# main.net
KiCad netlist of a schematic drawn in Altium Designer
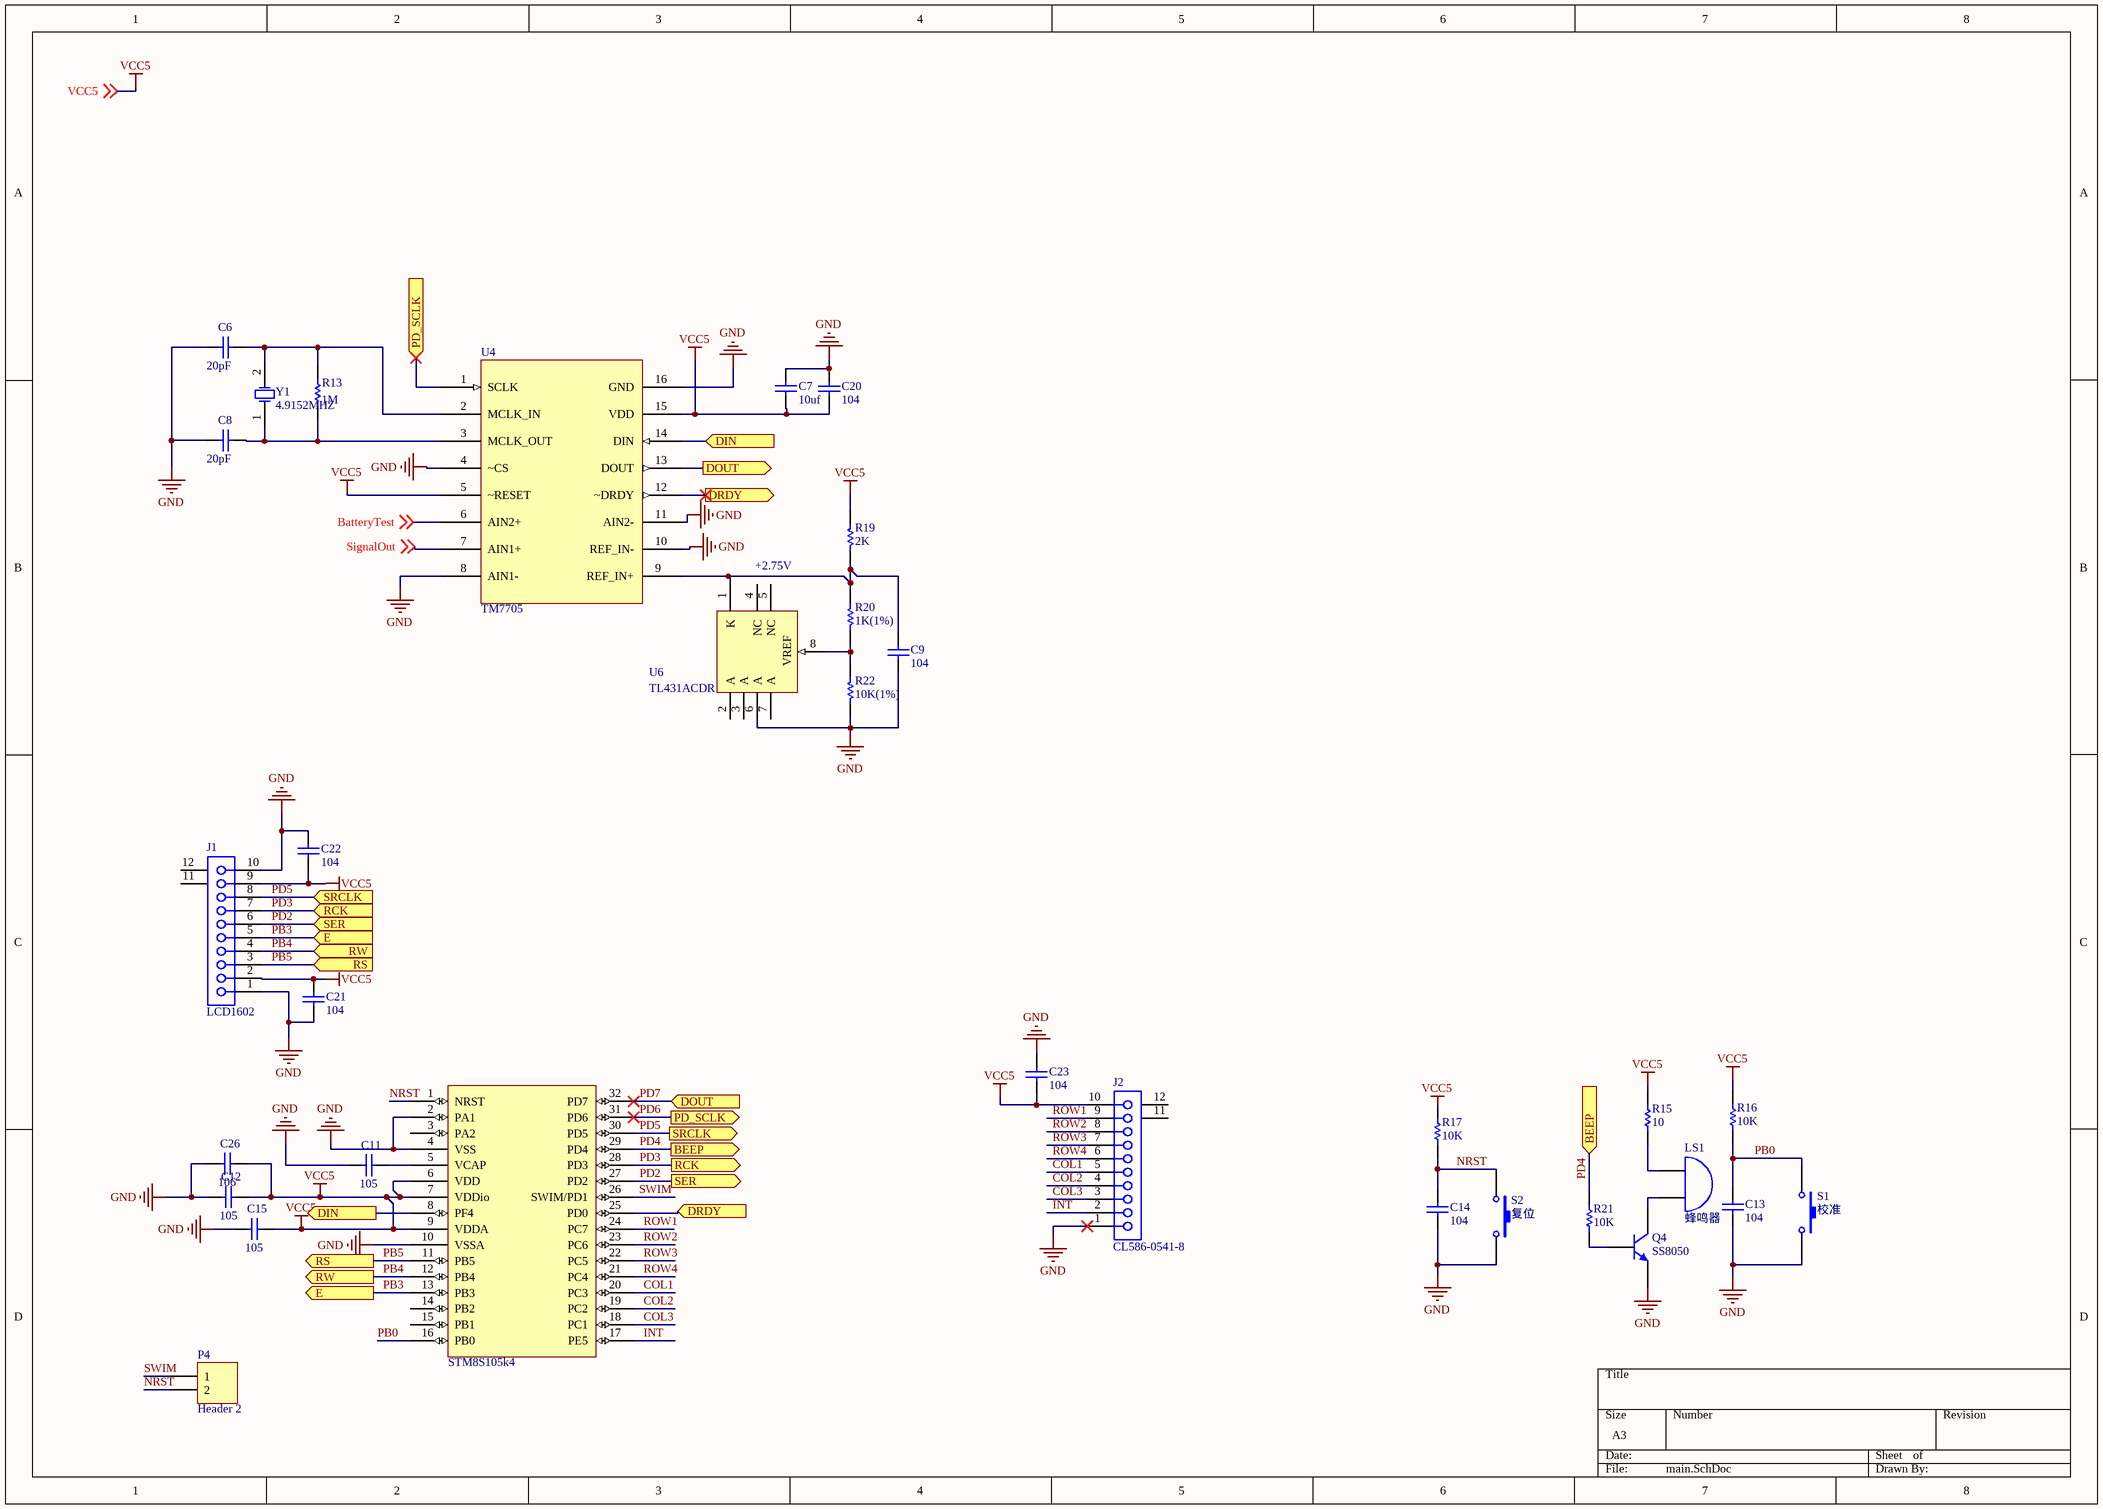
[diagram p0: main.SchDoc]

(export (version "E")
  (design (tool "Eeschema 10.0.6"))
  (components
    (comp (ref "C6")
      (value "20pF")
      (footprint "C0805")
      (description "Capacitor")
      (fields (field (name "Comment") "Cap") (field (name "PUBLISHER") "Altium Limited"))
      (libsource (lib "Miscellaneous Devices") (part "Cap"))
    )
    (comp (ref "C7")
      (value "10uf")
      (footprint "C0805")
      (description "Capacitor")
      (fields (field (name "Comment") "Cap") (field (name "PUBLISHER") "Altium Limited"))
      (libsource (lib "Miscellaneous Devices") (part "Cap"))
    )
    (comp (ref "C8")
      (value "20pF")
      (footprint "C0805")
      (description "Capacitor")
      (fields (field (name "Comment") "Cap") (field (name "PUBLISHER") "Altium Limited"))
      (libsource (lib "Miscellaneous Devices") (part "Cap"))
    )
    (comp (ref "C9")
      (value "104")
      (footprint "C0805")
      (description "Capacitor")
      (fields (field (name "Comment") "Cap") (field (name "PUBLISHER") "Altium Limited"))
      (libsource (lib "Miscellaneous Devices") (part "Cap"))
    )
    (comp (ref "C11")
      (value "105")
      (footprint "C0805")
      (description "Capacitor")
      (fields (field (name "Comment") "Cap") (field (name "PUBLISHER") "Altium Limited"))
      (libsource (lib "Miscellaneous Devices") (part "Cap"))
    )
    (comp (ref "C12")
      (value "105")
      (footprint "C0805")
      (description "Capacitor")
      (fields (field (name "Comment") "Cap") (field (name "PUBLISHER") "Altium Limited"))
      (libsource (lib "Miscellaneous Devices") (part "Cap"))
    )
    (comp (ref "C13")
      (value "104")
      (footprint "C0805")
      (description "Capacitor")
      (fields (field (name "Comment") "Cap") (field (name "PUBLISHER") "Altium Limited"))
      (libsource (lib "Miscellaneous Devices") (part "Cap"))
    )
    (comp (ref "C14")
      (value "104")
      (footprint "C0805")
      (description "Capacitor")
      (fields (field (name "Comment") "Cap") (field (name "PUBLISHER") "Altium Limited"))
      (libsource (lib "Miscellaneous Devices") (part "Cap"))
    )
    (comp (ref "C15")
      (value "105")
      (footprint "C0805")
      (description "Capacitor")
      (fields (field (name "Comment") "Cap") (field (name "PUBLISHER") "Altium Limited"))
      (libsource (lib "Miscellaneous Devices") (part "Cap"))
    )
    (comp (ref "C20")
      (value "104")
      (footprint "C0805")
      (description "Capacitor")
      (fields (field (name "Comment") "Cap") (field (name "PUBLISHER") "Altium Limited"))
      (libsource (lib "Miscellaneous Devices") (part "Cap"))
    )
    (comp (ref "C21")
      (value "104")
      (footprint "C0805")
      (description "Capacitor")
      (fields (field (name "Comment") "Cap") (field (name "PUBLISHER") "Altium Limited"))
      (libsource (lib "Miscellaneous Devices") (part "Cap"))
    )
    (comp (ref "C22")
      (value "104")
      (footprint "C0805")
      (description "Capacitor")
      (fields (field (name "Comment") "Cap") (field (name "PUBLISHER") "Altium Limited"))
      (libsource (lib "Miscellaneous Devices") (part "Cap"))
    )
    (comp (ref "C23")
      (value "104")
      (footprint "C0805")
      (description "Capacitor")
      (fields (field (name "Comment") "Cap") (field (name "PUBLISHER") "Altium Limited"))
      (libsource (lib "Miscellaneous Devices") (part "Cap"))
    )
    (comp (ref "C26")
      (value "106")
      (footprint "C0805")
      (description "Capacitor")
      (fields (field (name "Comment") "Cap") (field (name "PUBLISHER") "Altium Limited"))
      (libsource (lib "Miscellaneous Devices") (part "Cap"))
    )
    (comp (ref "J1")
      (value "LCD1602")
      (footprint "FH12-22(10)SA-1SH")
      (description "FH12 Series, \"Flip-Lock\" SMT/ZIF FFC/FPC Connector - 1.0mm Spaced Bottom Eccentric Contact")
      (fields (field (name "PUBLISHER") "Altium Limited"))
      (libsource (lib "HRS FPC-FFC FH12 Series") (part "CL586-0541-8"))
    )
    (comp (ref "J2")
      (value "CL586-0541-8")
      (footprint "FH12-22(10)SA-1SH")
      (description "FH12 Series, \"Flip-Lock\" SMT/ZIF FFC/FPC Connector - 1.0mm Spaced Bottom Eccentric Contact")
      (fields (field (name "PUBLISHER") "Altium Limited"))
      (libsource (lib "HRS FPC-FFC FH12 Series") (part "CL586-0541-8"))
    )
    (comp (ref "LS1")
      (value "蜂鸣器")
      (footprint "BELL")
      (description "Electrical Bell")
      (fields (field (name "PUBLISHER") "Altium Limited"))
      (libsource (lib "Miscellaneous Devices") (part "Bell"))
    )
    (comp (ref "P4")
      (value "Header 2")
      (footprint "HDR1X2")
      (description "Header, 2-Pin")
      (fields (field (name "PUBLISHER") "Altium Limited"))
      (libsource (lib "Miscellaneous Connectors") (part "Header 2"))
    )
    (comp (ref "Q4")
      (value "SS8050")
      (footprint "SOT-23_N")
      (description "NPN Bipolar Transistor")
      (fields (field (name "PUBLISHER") "Altium Limited"))
      (libsource (lib "Miscellaneous Devices") (part "NPN"))
    )
    (comp (ref "R13")
      (value "1M")
      (footprint "C1206")
      (description "Resistor")
      (fields (field (name "Comment") "Res1") (field (name "PUBLISHER") "Altium Limited"))
      (libsource (lib "Miscellaneous Devices") (part "Res1"))
    )
    (comp (ref "R15")
      (value "10")
      (footprint "C1206")
      (description "Resistor")
      (fields (field (name "Comment") "Res1") (field (name "PUBLISHER") "Altium Limited"))
      (libsource (lib "Miscellaneous Devices") (part "Res1"))
    )
    (comp (ref "R16")
      (value "10K")
      (footprint "6-0805_N")
      (description "Resistor")
      (fields (field (name "Comment") "Res1") (field (name "PUBLISHER") "Altium Limited"))
      (libsource (lib "Miscellaneous Devices") (part "Res1"))
    )
    (comp (ref "R17")
      (value "10K")
      (footprint "6-0805_N")
      (description "Resistor")
      (fields (field (name "Comment") "Res1") (field (name "PUBLISHER") "Altium Limited"))
      (libsource (lib "Miscellaneous Devices") (part "Res1"))
    )
    (comp (ref "R19")
      (value "2K")
      (footprint "6-0805_N")
      (description "Resistor")
      (fields (field (name "Comment") "Res1") (field (name "PUBLISHER") "Altium Limited"))
      (libsource (lib "Miscellaneous Devices") (part "Res1"))
    )
    (comp (ref "R20")
      (value "1K(1%)")
      (footprint "6-0805_N")
      (description "Resistor")
      (fields (field (name "Comment") "Res1") (field (name "PUBLISHER") "Altium Limited"))
      (libsource (lib "Miscellaneous Devices") (part "Res1"))
    )
    (comp (ref "R21")
      (value "10K")
      (footprint "6-0805_N")
      (description "Resistor")
      (fields (field (name "Comment") "Res1") (field (name "PUBLISHER") "Altium Limited"))
      (libsource (lib "Miscellaneous Devices") (part "Res1"))
    )
    (comp (ref "R22")
      (value "10K(1%)")
      (footprint "6-0805_N")
      (description "Resistor")
      (fields (field (name "Comment") "Res1") (field (name "PUBLISHER") "Altium Limited"))
      (libsource (lib "Miscellaneous Devices") (part "Res1"))
    )
    (comp (ref "S1")
      (value "校准")
      (footprint "buttin12*12")
      (description "Switch")
      (fields (field (name "PUBLISHER") "Altium Limited"))
      (libsource (lib "Miscellaneous Devices") (part "SW-PB"))
    )
    (comp (ref "S2")
      (value "复位")
      (footprint "buttin6*6")
      (description "Switch")
      (fields (field (name "PUBLISHER") "Altium Limited"))
      (libsource (lib "Miscellaneous Devices") (part "SW-PB"))
    )
    (comp (ref "STM1") (value "STM8S105k4") (footprint "LQFP32") (libsource (lib "self") (part "STM8S105k4")))
    (comp (ref "U4") (value "TM7705") (footprint "SO16_N") (libsource (lib "Schlib1") (part "TM7705")))
    (comp (ref "U6")
      (value "TL431ACDR")
      (footprint "D008_N")
      (description "Adjustable Precision Shunt Regulator")
      (fields (field (name "PUBLISHER") "Altium Limited"))
      (libsource (lib "TI Power Mgt Voltage Regulator") (part "TL431ACDR"))
    )
    (comp (ref "Y1")
      (value "4.9152MHZ")
      (footprint "XTAL-HC49US2")
      (description "Crystal Oscillator")
      (fields (field (name "PUBLISHER") "Altium Limited"))
      (libsource (lib "Miscellaneous Devices") (part "XTAL"))
    )
  )
  (nets
    (net (code "2") (name "/COL1") (class "Default")
      (node (ref "J2") (pin "5") (pinfunction "5_5") (pintype "passive"))
      (node (ref "STM1") (pin "20") (pinfunction "PC3_20") (pintype "bidirectional"))
    )
    (net (code "3") (name "/COL2") (class "Default")
      (node (ref "J2") (pin "4") (pinfunction "4_4") (pintype "passive"))
      (node (ref "STM1") (pin "19") (pinfunction "PC2_19") (pintype "bidirectional"))
    )
    (net (code "4") (name "/COL3") (class "Default")
      (node (ref "J2") (pin "3") (pinfunction "3_3") (pintype "passive"))
      (node (ref "STM1") (pin "18") (pinfunction "PC1_18") (pintype "bidirectional"))
    )
    (net (code "5") (name "/DIN") (class "Default")
      (node (ref "STM1") (pin "8") (pinfunction "PF4_8") (pintype "bidirectional"))
      (node (ref "U4") (pin "14") (pinfunction "DIN_14") (pintype "input"))
    )
    (net (code "6") (name "/DRDY") (class "Default")
      (node (ref "STM1") (pin "25") (pinfunction "PD0_25") (pintype "bidirectional"))
      (node (ref "U4") (pin "12") (pinfunction "~DRDY_12") (pintype "output"))
    )
    (net (code "7") (name "/INT") (class "Default")
      (node (ref "J2") (pin "2") (pinfunction "2_2") (pintype "passive"))
      (node (ref "STM1") (pin "17") (pinfunction "PE5_17") (pintype "bidirectional"))
    )
    (net (code "8") (name "/NRST") (class "Default")
      (node (ref "C14") (pin "2") (pinfunction "2_2") (pintype "passive"))
      (node (ref "P4") (pin "2") (pinfunction "2_2") (pintype "passive"))
      (node (ref "R17") (pin "2") (pinfunction "2_2") (pintype "passive"))
      (node (ref "S2") (pin "1") (pinfunction "1_1") (pintype "passive"))
      (node (ref "STM1") (pin "1") (pinfunction "NRST_1") (pintype "bidirectional"))
    )
    (net (code "9") (name "/PB0") (class "Default")
      (node (ref "C13") (pin "2") (pinfunction "2_2") (pintype "passive"))
      (node (ref "R16") (pin "2") (pinfunction "2_2") (pintype "passive"))
      (node (ref "S1") (pin "1") (pinfunction "1_1") (pintype "passive"))
      (node (ref "STM1") (pin "16") (pinfunction "PB0_16") (pintype "bidirectional"))
    )
    (net (code "10") (name "/PB3") (class "Default")
      (node (ref "J1") (pin "5") (pinfunction "5_5") (pintype "passive"))
      (node (ref "STM1") (pin "13") (pinfunction "PB3_13") (pintype "bidirectional"))
    )
    (net (code "11") (name "/PB4") (class "Default")
      (node (ref "J1") (pin "4") (pinfunction "4_4") (pintype "passive"))
      (node (ref "STM1") (pin "12") (pinfunction "PB4_12") (pintype "bidirectional"))
    )
    (net (code "12") (name "/PB5") (class "Default")
      (node (ref "J1") (pin "3") (pinfunction "3_3") (pintype "passive"))
      (node (ref "STM1") (pin "11") (pinfunction "PB5_11") (pintype "bidirectional"))
    )
    (net (code "13") (name "/PD2") (class "Default")
      (node (ref "J1") (pin "6") (pinfunction "6_6") (pintype "passive"))
      (node (ref "STM1") (pin "27") (pinfunction "PD2_27") (pintype "bidirectional"))
    )
    (net (code "14") (name "/PD3") (class "Default")
      (node (ref "J1") (pin "7") (pinfunction "7_7") (pintype "passive"))
      (node (ref "STM1") (pin "28") (pinfunction "PD3_28") (pintype "bidirectional"))
    )
    (net (code "15") (name "/PD4") (class "Default")
      (node (ref "R21") (pin "2") (pinfunction "2_2") (pintype "passive"))
      (node (ref "STM1") (pin "29") (pinfunction "PD4_29") (pintype "bidirectional"))
    )
    (net (code "16") (name "/PD5") (class "Default")
      (node (ref "J1") (pin "8") (pinfunction "8_8") (pintype "passive"))
      (node (ref "STM1") (pin "30") (pinfunction "PD5_30") (pintype "bidirectional"))
    )
    (net (code "17") (name "/PD6") (class "Default")
      (node (ref "STM1") (pin "31") (pinfunction "PD6_31") (pintype "bidirectional"))
      (node (ref "U4") (pin "1") (pinfunction "SCLK_1") (pintype "input"))
    )
    (net (code "18") (name "/PD7") (class "Default")
      (node (ref "STM1") (pin "32") (pinfunction "PD7_32") (pintype "bidirectional"))
      (node (ref "U4") (pin "13") (pinfunction "DOUT_13") (pintype "output"))
    )
    (net (code "19") (name "/ROW1") (class "Default")
      (node (ref "J2") (pin "9") (pinfunction "9_9") (pintype "passive"))
      (node (ref "STM1") (pin "24") (pinfunction "PC7_24") (pintype "bidirectional"))
    )
    (net (code "20") (name "/ROW2") (class "Default")
      (node (ref "J2") (pin "8") (pinfunction "8_8") (pintype "passive"))
      (node (ref "STM1") (pin "23") (pinfunction "PC6_23") (pintype "bidirectional"))
    )
    (net (code "21") (name "/ROW3") (class "Default")
      (node (ref "J2") (pin "7") (pinfunction "7_7") (pintype "passive"))
      (node (ref "STM1") (pin "22") (pinfunction "PC5_22") (pintype "bidirectional"))
    )
    (net (code "22") (name "/ROW4") (class "Default")
      (node (ref "J2") (pin "6") (pinfunction "6_6") (pintype "passive"))
      (node (ref "STM1") (pin "21") (pinfunction "PC4_21") (pintype "bidirectional"))
    )
    (net (code "23") (name "/SWIM") (class "Default")
      (node (ref "P4") (pin "1") (pinfunction "1_1") (pintype "passive"))
      (node (ref "STM1") (pin "26") (pinfunction "SWIM/PD1_26") (pintype "bidirectional"))
    )
    (net (code "24") (name "BatteryTest") (class "Default")
      (node (ref "U4") (pin "6") (pinfunction "AIN2+_6") (pintype "passive"))
    )
    (net (code "25") (name "GND") (class "Default")
      (node (ref "C11") (pin "1") (pinfunction "1_1") (pintype "passive"))
      (node (ref "C12") (pin "1") (pinfunction "1_1") (pintype "passive"))
      (node (ref "C13") (pin "1") (pinfunction "1_1") (pintype "passive"))
      (node (ref "C14") (pin "1") (pinfunction "1_1") (pintype "passive"))
      (node (ref "C15") (pin "1") (pinfunction "1_1") (pintype "passive"))
      (node (ref "C20") (pin "2") (pinfunction "2_2") (pintype "passive"))
      (node (ref "C21") (pin "2") (pinfunction "2_2") (pintype "passive"))
      (node (ref "C22") (pin "1") (pinfunction "1_1") (pintype "passive"))
      (node (ref "C23") (pin "2") (pinfunction "2_2") (pintype "passive"))
      (node (ref "C26") (pin "1") (pinfunction "1_1") (pintype "passive"))
      (node (ref "C6") (pin "1") (pinfunction "1_1") (pintype "passive"))
      (node (ref "C7") (pin "2") (pinfunction "2_2") (pintype "passive"))
      (node (ref "C8") (pin "1") (pinfunction "1_1") (pintype "passive"))
      (node (ref "C9") (pin "1") (pinfunction "1_1") (pintype "passive"))
      (node (ref "J1") (pin "1") (pinfunction "1_1") (pintype "passive"))
      (node (ref "J1") (pin "10") (pinfunction "10_10") (pintype "passive"))
      (node (ref "J2") (pin "1") (pinfunction "1_1") (pintype "passive"))
      (node (ref "Q4") (pin "3") (pinfunction "E_3") (pintype "passive"))
      (node (ref "R22") (pin "2") (pinfunction "2_2") (pintype "passive"))
      (node (ref "S1") (pin "2") (pinfunction "2_2") (pintype "passive"))
      (node (ref "S2") (pin "2") (pinfunction "2_2") (pintype "passive"))
      (node (ref "STM1") (pin "10") (pinfunction "VSSA_10") (pintype "passive"))
      (node (ref "STM1") (pin "2") (pinfunction "PA1_2") (pintype "bidirectional"))
      (node (ref "STM1") (pin "4") (pinfunction "VSS_4") (pintype "passive"))
      (node (ref "U4") (pin "10") (pinfunction "REF_IN-_10") (pintype "passive"))
      (node (ref "U4") (pin "11") (pinfunction "AIN2-_11") (pintype "passive"))
      (node (ref "U4") (pin "16") (pinfunction "GND_16") (pintype "passive"))
      (node (ref "U4") (pin "4") (pinfunction "~CS_4") (pintype "passive"))
      (node (ref "U4") (pin "8") (pinfunction "AIN1-_8") (pintype "passive"))
      (node (ref "U6") (pin "6") (pinfunction "A_6") (pintype "power_in"))
    )
    (net (code "26") (name "Net-(LS1-A)") (class "Default")
      (node (ref "LS1") (pin "1") (pinfunction "A_1") (pintype "passive"))
      (node (ref "R15") (pin "2") (pinfunction "2_2") (pintype "passive"))
    )
    (net (code "27") (name "Net-(LS1-B)") (class "Default")
      (node (ref "LS1") (pin "2") (pinfunction "B_2") (pintype "passive"))
      (node (ref "Q4") (pin "1") (pinfunction "C_1") (pintype "passive"))
    )
    (net (code "28") (name "Net-(Q4-B)") (class "Default")
      (node (ref "Q4") (pin "2") (pinfunction "B_2") (pintype "passive"))
      (node (ref "R21") (pin "1") (pinfunction "1_1") (pintype "passive"))
    )
    (net (code "29") (name "Net-(STM1-VCAP)") (class "Default")
      (node (ref "C11") (pin "2") (pinfunction "2_2") (pintype "passive"))
      (node (ref "STM1") (pin "5") (pinfunction "VCAP_5") (pintype "passive"))
    )
    (net (code "30") (name "Net-(U4-MCLK_IN)") (class "Default")
      (node (ref "C6") (pin "2") (pinfunction "2_2") (pintype "passive"))
      (node (ref "R13") (pin "1") (pinfunction "1_1") (pintype "passive"))
      (node (ref "U4") (pin "2") (pinfunction "MCLK_IN_2") (pintype "passive"))
      (node (ref "Y1") (pin "2") (pinfunction "OSC2_2") (pintype "passive"))
    )
    (net (code "31") (name "Net-(U4-MCLK_OUT)") (class "Default")
      (node (ref "C8") (pin "2") (pinfunction "2_2") (pintype "passive"))
      (node (ref "R13") (pin "2") (pinfunction "2_2") (pintype "passive"))
      (node (ref "U4") (pin "3") (pinfunction "MCLK_OUT_3") (pintype "passive"))
      (node (ref "Y1") (pin "1") (pinfunction "OSC1_1") (pintype "passive"))
    )
    (net (code "32") (name "Net-(U4-REF_IN+)") (class "Default")
      (node (ref "C9") (pin "2") (pinfunction "2_2") (pintype "passive"))
      (node (ref "R19") (pin "2") (pinfunction "2_2") (pintype "passive"))
      (node (ref "R20") (pin "1") (pinfunction "1_1") (pintype "passive"))
      (node (ref "U4") (pin "9") (pinfunction "REF_IN+_9") (pintype "passive"))
      (node (ref "U6") (pin "1") (pinfunction "K_1") (pintype "power_in"))
    )
    (net (code "33") (name "Net-(U6-VREF)") (class "Default")
      (node (ref "R20") (pin "2") (pinfunction "2_2") (pintype "passive"))
      (node (ref "R22") (pin "1") (pinfunction "1_1") (pintype "passive"))
      (node (ref "U6") (pin "8") (pinfunction "VREF_8") (pintype "input"))
    )
    (net (code "34") (name "SignalOut") (class "Default")
      (node (ref "U4") (pin "7") (pinfunction "AIN1+_7") (pintype "passive"))
    )
    (net (code "35") (name "VCC5") (class "Default")
      (node (ref "C12") (pin "2") (pinfunction "2_2") (pintype "passive"))
      (node (ref "C15") (pin "2") (pinfunction "2_2") (pintype "passive"))
      (node (ref "C20") (pin "1") (pinfunction "1_1") (pintype "passive"))
      (node (ref "C21") (pin "1") (pinfunction "1_1") (pintype "passive"))
      (node (ref "C22") (pin "2") (pinfunction "2_2") (pintype "passive"))
      (node (ref "C23") (pin "1") (pinfunction "1_1") (pintype "passive"))
      (node (ref "C26") (pin "2") (pinfunction "2_2") (pintype "passive"))
      (node (ref "C7") (pin "1") (pinfunction "1_1") (pintype "passive"))
      (node (ref "J1") (pin "2") (pinfunction "2_2") (pintype "passive"))
      (node (ref "J1") (pin "9") (pinfunction "9_9") (pintype "passive"))
      (node (ref "J2") (pin "10") (pinfunction "10_10") (pintype "passive"))
      (node (ref "R15") (pin "1") (pinfunction "1_1") (pintype "passive"))
      (node (ref "R16") (pin "1") (pinfunction "1_1") (pintype "passive"))
      (node (ref "R17") (pin "1") (pinfunction "1_1") (pintype "passive"))
      (node (ref "R19") (pin "1") (pinfunction "1_1") (pintype "passive"))
      (node (ref "STM1") (pin "6") (pinfunction "VDD_6") (pintype "passive"))
      (node (ref "STM1") (pin "7") (pinfunction "VDDio_7") (pintype "passive"))
      (node (ref "STM1") (pin "9") (pinfunction "VDDA_9") (pintype "passive"))
      (node (ref "U4") (pin "15") (pinfunction "VDD_15") (pintype "passive"))
      (node (ref "U4") (pin "5") (pinfunction "~RESET_5") (pintype "passive"))
    )
    (net (code "36") (name "unconnected-(J1-MH1-Pad11)") (class "Default")
      (node (ref "J1") (pin "11") (pinfunction "MH1_11") (pintype "passive"))
    )
    (net (code "37") (name "unconnected-(J1-MH2-Pad12)") (class "Default")
      (node (ref "J1") (pin "12") (pinfunction "MH2_12") (pintype "passive"))
    )
    (net (code "38") (name "unconnected-(J2-MH1-Pad11)") (class "Default")
      (node (ref "J2") (pin "11") (pinfunction "MH1_11") (pintype "passive"))
    )
    (net (code "39") (name "unconnected-(J2-MH2-Pad12)") (class "Default")
      (node (ref "J2") (pin "12") (pinfunction "MH2_12") (pintype "passive"))
    )
    (net (code "40") (name "unconnected-(STM1-PA2-Pad3)") (class "Default")
      (node (ref "STM1") (pin "3") (pinfunction "PA2_3") (pintype "bidirectional"))
    )
    (net (code "41") (name "unconnected-(STM1-PB1-Pad15)") (class "Default")
      (node (ref "STM1") (pin "15") (pinfunction "PB1_15") (pintype "bidirectional"))
    )
    (net (code "42") (name "unconnected-(STM1-PB2-Pad14)") (class "Default")
      (node (ref "STM1") (pin "14") (pinfunction "PB2_14") (pintype "bidirectional"))
    )
    (net (code "43") (name "unconnected-(U6-A-Pad2)") (class "Default")
      (node (ref "U6") (pin "2") (pinfunction "A_2") (pintype "power_in"))
    )
    (net (code "44") (name "unconnected-(U6-A-Pad3)") (class "Default")
      (node (ref "U6") (pin "3") (pinfunction "A_3") (pintype "power_in"))
    )
    (net (code "45") (name "unconnected-(U6-A-Pad7)") (class "Default")
      (node (ref "U6") (pin "7") (pinfunction "A_7") (pintype "power_in"))
    )
    (net (code "46") (name "unconnected-(U6-NC-Pad4)") (class "Default")
      (node (ref "U6") (pin "4") (pinfunction "NC_4") (pintype "passive"))
    )
    (net (code "47") (name "unconnected-(U6-NC-Pad5)") (class "Default")
      (node (ref "U6") (pin "5") (pinfunction "NC_5") (pintype "passive"))
    )
  )
)
